# design.net
KiCad netlist of a schematic drawn in Altium Designer
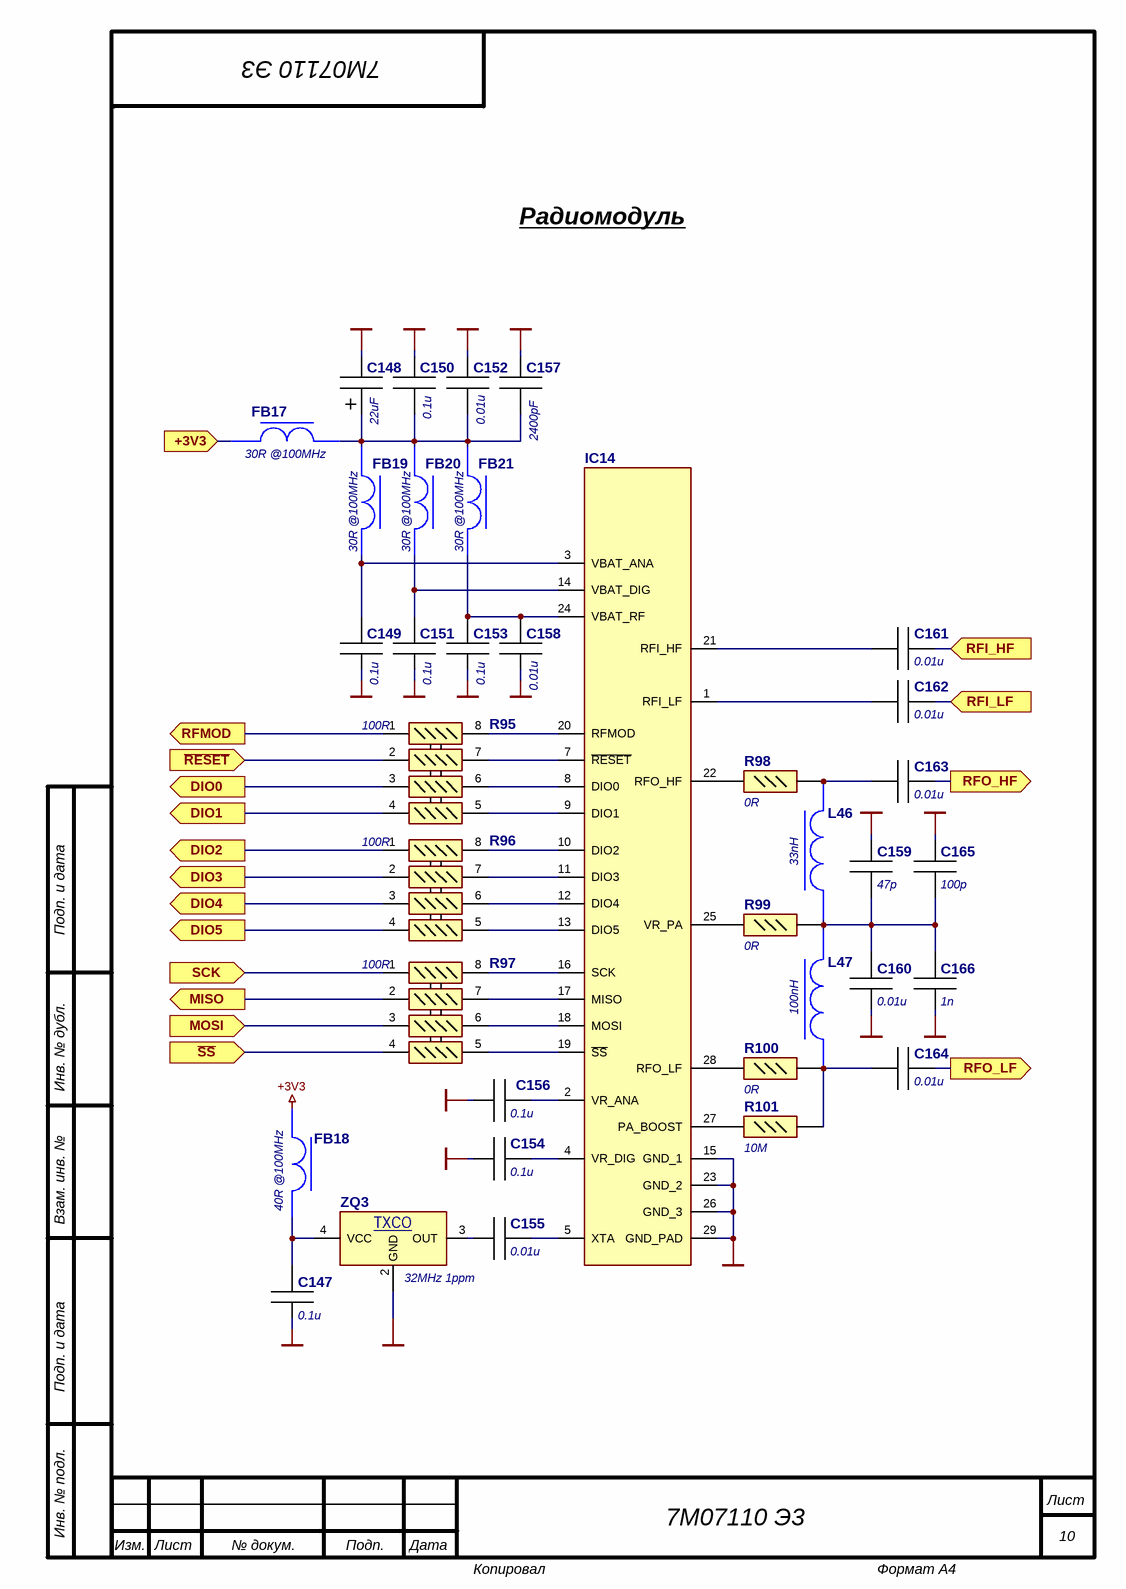
[diagram p0: Радиомодуль.SchDoc]

(export (version "E")
  (design (tool "Eeschema 10.0.6"))
  (components
    (comp (ref "C147")
      (value "0.1u")
      (footprint ":CAP0402 100x50x50")
      (description "±10% 25V Ceramic Capacitor X7R 0402 (1005 Metric)")
      (fields
        (field (name "MANUFACTURER_PART_NUMBER") "GRM155R71E104KE14J")
        (field (name "MOUSER PART NUMBER") "81-GRM155R71E104KE4J")
      )
      (libsource (lib "Capacitors 0402") (part "GRM155R71E104KE14J"))
    )
    (comp (ref "C148")
      (value "22uF")
      (footprint ":CAP1206 C3216-18")
      (description "22µF Molded Tantalum Capacitors 6.3V 1206 (3216 Metric) 300mOhm @ 100kHz")
      (fields (field (name "MANUFACTURER_PART_NUMBER") "TPSA226K006R0300"))
      (libsource (lib "Capacitors 1206") (part "TPSA226K006R0300"))
    )
    (comp (ref "C149")
      (value "0.1u")
      (footprint ":CAP0402 100x50x50")
      (description "±10% 25V Ceramic Capacitor X7R 0402 (1005 Metric)")
      (fields
        (field (name "MANUFACTURER_PART_NUMBER") "GRM155R71E104KE14J")
        (field (name "MOUSER PART NUMBER") "81-GRM155R71E104KE4J")
      )
      (libsource (lib "Capacitors 0402") (part "GRM155R71E104KE14J"))
    )
    (comp (ref "C150")
      (value "0.1u")
      (footprint ":CAP0402 100x50x50")
      (description "±10% 25V Ceramic Capacitor X7R 0402 (1005 Metric)")
      (fields
        (field (name "MANUFACTURER_PART_NUMBER") "GRM155R71E104KE14J")
        (field (name "MOUSER PART NUMBER") "81-GRM155R71E104KE4J")
      )
      (libsource (lib "Capacitors 0402") (part "GRM155R71E104KE14J"))
    )
    (comp (ref "C151")
      (value "0.1u")
      (footprint ":CAP0402 100x50x50")
      (description "±10% 25V Ceramic Capacitor X7R 0402 (1005 Metric)")
      (fields
        (field (name "MANUFACTURER_PART_NUMBER") "GRM155R71E104KE14J")
        (field (name "MOUSER PART NUMBER") "81-GRM155R71E104KE4J")
      )
      (libsource (lib "Capacitors 0402") (part "GRM155R71E104KE14J"))
    )
    (comp (ref "C152")
      (value "0.01u")
      (footprint ":CAP0402 100x50x50")
      (description "±5% 35V Ceramic Capacitor C0G, NP0 0402 (1005 Metric)")
      (fields (field (name "MANUFACTURER_PART_NUMBER") "GRM1555CYA103JE01D"))
      (libsource (lib "Capacitors 0402") (part "GRM1555CYA103JE01D"))
    )
    (comp (ref "C153")
      (value "0.1u")
      (footprint ":CAP0402 100x50x50")
      (description "±10% 25V Ceramic Capacitor X7R 0402 (1005 Metric)")
      (fields
        (field (name "MANUFACTURER_PART_NUMBER") "GRM155R71E104KE14J")
        (field (name "MOUSER PART NUMBER") "81-GRM155R71E104KE4J")
      )
      (libsource (lib "Capacitors 0402") (part "GRM155R71E104KE14J"))
    )
    (comp (ref "C154")
      (value "0.1u")
      (footprint ":CAP0402 100x50x50")
      (description "±10% 25V Ceramic Capacitor X7R 0402 (1005 Metric)")
      (fields
        (field (name "MANUFACTURER_PART_NUMBER") "GRM155R71E104KE14J")
        (field (name "MOUSER PART NUMBER") "81-GRM155R71E104KE4J")
      )
      (libsource (lib "Capacitors 0402") (part "GRM155R71E104KE14J"))
    )
    (comp (ref "C155")
      (value "0.01u")
      (footprint ":CAP0402 100x50x50")
      (description "±5% 35V Ceramic Capacitor C0G, NP0 0402 (1005 Metric)")
      (fields (field (name "MANUFACTURER_PART_NUMBER") "GRM1555CYA103JE01D"))
      (libsource (lib "Capacitors 0402") (part "GRM1555CYA103JE01D"))
    )
    (comp (ref "C156")
      (value "0.1u")
      (footprint ":CAP0402 100x50x50")
      (description "±10% 25V Ceramic Capacitor X7R 0402 (1005 Metric)")
      (fields
        (field (name "MANUFACTURER_PART_NUMBER") "GRM155R71E104KE14J")
        (field (name "MOUSER PART NUMBER") "81-GRM155R71E104KE4J")
      )
      (libsource (lib "Capacitors 0402") (part "GRM155R71E104KE14J"))
    )
    (comp (ref "C157")
      (value "2400pF")
      (footprint ":CAP0805 C2012X125")
      (description "2400pF 50V Ceramic Capacitor 0805 (2012 Metric)")
      (fields (field (name "MANUFACTURER_PART_NUMBER") "C08BL242X-5UN-X0T"))
      (libsource (lib "Capacitors 0805") (part "C08BL242X-5UN-X0T"))
    )
    (comp (ref "C158")
      (value "0.01u")
      (footprint ":CAP0402 100x50x50")
      (description "±5% 35V Ceramic Capacitor C0G, NP0 0402 (1005 Metric)")
      (fields (field (name "MANUFACTURER_PART_NUMBER") "GRM1555CYA103JE01D"))
      (libsource (lib "Capacitors 0402") (part "GRM1555CYA103JE01D"))
    )
    (comp (ref "C159")
      (value "47p")
      (footprint ":CAP0402 100x50x50")
      (description "CAP CER  50V C0G/NP0 0402")
      (fields (field (name "MANUFACTURER_PART_NUMBER") "GJM1555C1H470GB01D"))
      (libsource (lib "Capacitors 0402") (part "GJM1555C1H470GB01D"))
    )
    (comp (ref "C160")
      (value "0.01u")
      (footprint ":CAP0402 100x50x50")
      (description "±5% 35V Ceramic Capacitor C0G, NP0 0402 (1005 Metric)")
      (fields (field (name "MANUFACTURER_PART_NUMBER") "GRM1555CYA103JE01D"))
      (libsource (lib "Capacitors 0402") (part "GRM1555CYA103JE01D"))
    )
    (comp (ref "C161")
      (value "0.01u")
      (footprint ":CAP0402 100x50x50")
      (description "±5% 35V Ceramic Capacitor C0G, NP0 0402 (1005 Metric)")
      (fields (field (name "MANUFACTURER_PART_NUMBER") "GRM1555CYA103JE01D"))
      (libsource (lib "Capacitors 0402") (part "GRM1555CYA103JE01D"))
    )
    (comp (ref "C162")
      (value "0.01u")
      (footprint ":CAP0402 100x50x50")
      (description "±5% 35V Ceramic Capacitor C0G, NP0 0402 (1005 Metric)")
      (fields (field (name "MANUFACTURER_PART_NUMBER") "GRM1555CYA103JE01D"))
      (libsource (lib "Capacitors 0402") (part "GRM1555CYA103JE01D"))
    )
    (comp (ref "C163")
      (value "0.01u")
      (footprint ":CAP0402 100x50x50")
      (description "±5% 35V Ceramic Capacitor C0G, NP0 0402 (1005 Metric)")
      (fields (field (name "MANUFACTURER_PART_NUMBER") "GRM1555CYA103JE01D"))
      (libsource (lib "Capacitors 0402") (part "GRM1555CYA103JE01D"))
    )
    (comp (ref "C164")
      (value "0.01u")
      (footprint ":CAP0402 100x50x50")
      (description "±5% 35V Ceramic Capacitor C0G, NP0 0402 (1005 Metric)")
      (fields (field (name "MANUFACTURER_PART_NUMBER") "GRM1555CYA103JE01D"))
      (libsource (lib "Capacitors 0402") (part "GRM1555CYA103JE01D"))
    )
    (comp (ref "C165")
      (value "100p")
      (footprint ":CAP0402 100x50x50")
      (description "CAP CER  50V C0G/NP0 0402")
      (fields (field (name "MANUFACTURER_PART_NUMBER") "GCM1555C1H101JA16D"))
      (libsource (lib "Capacitors 0402") (part "GCM1555C1H101JA16D"))
    )
    (comp (ref "C166")
      (value "1n")
      (footprint ":CAP0402 100x50x50")
      (description "±5% 50V Ceramic Capacitor C0G, NP0 0402 (1005 Metric)")
      (fields (field (name "MANUFACTURER_PART_NUMBER") "GRM1555C1H102JA01J"))
      (libsource (lib "Capacitors 0402") (part "GRM1555C1H102JA01J"))
    )
    (comp (ref "FB17")
      (value "30R @100MHz")
      (footprint ":FER BLM18SP300SN1D")
      (description "30 Ohms @ 100MHz 1 Power Line Ferrite Bead 0603 (1608 Metric) 6A 8mOhm")
      (fields
        (field (name "MANUFACTURER_PART_NUMBER") "BLM18SP300SN1D")
        (field (name "MOUSER PART NUMBER") "81-BLM18SP300SN1D")
      )
      (libsource (lib "Ferrite Bead") (part "BLM18SP300SN1D"))
    )
    (comp (ref "FB18")
      (value "40R @100MHz")
      (footprint ":FER MMZ1005Y400CTD25")
      (description "40 Ohms @ 100MHz 1 Signal Line Ferrite Bead 0402 (1005 Metric) 550mA 100mOhm")
      (fields
        (field (name "MANUFACTURER_PART_NUMBER") "MMZ1005Y400CTD25")
        (field (name "MOUSER PART NUMBER") "810-MMZ1005Y400CTD25")
      )
      (libsource (lib "Ferrite Bead") (part "MMZ1005Y400CTD25"))
    )
    (comp (ref "FB19")
      (value "30R @100MHz")
      (footprint ":FER BLM18SP300SN1D")
      (description "30 Ohms @ 100MHz 1 Power Line Ferrite Bead 0603 (1608 Metric) 6A 8mOhm")
      (fields
        (field (name "MANUFACTURER_PART_NUMBER") "BLM18SP300SN1D")
        (field (name "MOUSER PART NUMBER") "81-BLM18SP300SN1D")
      )
      (libsource (lib "Ferrite Bead") (part "BLM18SP300SN1D"))
    )
    (comp (ref "FB20")
      (value "30R @100MHz")
      (footprint ":FER BLM18SP300SN1D")
      (description "30 Ohms @ 100MHz 1 Power Line Ferrite Bead 0603 (1608 Metric) 6A 8mOhm")
      (fields
        (field (name "MANUFACTURER_PART_NUMBER") "BLM18SP300SN1D")
        (field (name "MOUSER PART NUMBER") "81-BLM18SP300SN1D")
      )
      (libsource (lib "Ferrite Bead") (part "BLM18SP300SN1D"))
    )
    (comp (ref "FB21")
      (value "30R @100MHz")
      (footprint ":FER BLM18SP300SN1D")
      (description "30 Ohms @ 100MHz 1 Power Line Ferrite Bead 0603 (1608 Metric) 6A 8mOhm")
      (fields
        (field (name "MANUFACTURER_PART_NUMBER") "BLM18SP300SN1D")
        (field (name "MOUSER PART NUMBER") "81-BLM18SP300SN1D")
      )
      (libsource (lib "Ferrite Bead") (part "BLM18SP300SN1D"))
    )
    (comp (ref "IC14")
      (value "SX1276IMLTRT")
      (footprint ":QFN28 P600X600X100-29N-D")
      (description "LoRa RF Transceiver 3 BANDS")
      (fields (field (name "MOUSER PART NUMBER") "947-SX1276IMLTRT"))
      (libsource (lib "Digital ICs") (part "SX1276IMLTRT"))
    )
    (comp (ref "L46")
      (value "33nH")
      (footprint ":IND 0603 (1608)")
      (description "Unshielded Multilayer Inductor 0603 5%")
      (fields (field (name "MANUFACTURER_PART_NUMBER") "LQW18AN33NJ8ZD"))
      (libsource (lib "Inductance 0603") (part "LQW18AN33NJ8ZD"))
    )
    (comp (ref "L47")
      (value "100nH")
      (footprint ":IND 0603 (1608)")
      (description "Unshielded Multilayer Inductor 0603 5%")
      (fields (field (name "MANUFACTURER_PART_NUMBER") "LQW18ANR10J8ZD"))
      (libsource (lib "Inductance 0603") (part "LQW18ANR10J8ZD"))
    )
    (comp (ref "R95")
      (value "100R")
      (footprint ":RES0402x4")
      (fields
        (field (name "MANUFACTURER_PART_NUMBER") "EXB-N8V101JX")
        (field (name "MOUSER PART NUMBER") "667-EXB-N8V101JX")
      )
      (libsource (lib "Resistors Arrays") (part "EXB-N8V101JX"))
    )
    (comp (ref "R96")
      (value "100R")
      (footprint ":RES0402x4")
      (fields
        (field (name "MANUFACTURER_PART_NUMBER") "EXB-N8V101JX")
        (field (name "MOUSER PART NUMBER") "667-EXB-N8V101JX")
      )
      (libsource (lib "Resistors Arrays") (part "EXB-N8V101JX"))
    )
    (comp (ref "R97")
      (value "100R")
      (footprint ":RES0402x4")
      (fields
        (field (name "MANUFACTURER_PART_NUMBER") "EXB-N8V101JX")
        (field (name "MOUSER PART NUMBER") "667-EXB-N8V101JX")
      )
      (libsource (lib "Resistors Arrays") (part "EXB-N8V101JX"))
    )
    (comp (ref "R98")
      (value "RC0402FR-07")
      (footprint ":RES0402")
      (fields (field (name "MANUFACTURER_PART_NUMBER (PART 2: VALUE)") "0R"))
      (libsource (lib "Resistors 0402") (part "RC0402FR-07"))
    )
    (comp (ref "R99")
      (value "RC0402FR-07")
      (footprint ":RES0402")
      (fields (field (name "MANUFACTURER_PART_NUMBER (PART 2: VALUE)") "0R"))
      (libsource (lib "Resistors 0402") (part "RC0402FR-07"))
    )
    (comp (ref "R100")
      (value "RC0402FR-07")
      (footprint ":RES0402")
      (fields (field (name "MANUFACTURER_PART_NUMBER (PART 2: VALUE)") "0R"))
      (libsource (lib "Resistors 0402") (part "RC0402FR-07"))
    )
    (comp (ref "R101")
      (value "RC0402FR-07")
      (footprint ":RES0402")
      (fields (field (name "MANUFACTURER_PART_NUMBER (PART 2: VALUE)") "10M"))
      (libsource (lib "Resistors 0402") (part "RC0402FR-07"))
    )
    (comp (ref "ZQ3")
      (value "32MHz 1ppm")
      (footprint ":RESO STC22K33R48-32.000MT")
      (description "32MHz TCXO Clipped Sine Wave Oscillator 3.3V 2mA 4-SMD, \r\n-40°C ~ 85°C")
      (fields (field (name "MANUFACTURER_PART_NUMBER") "STC22K33R48-32.000MT"))
      (libsource (lib "Crystal and TXCO") (part "STC22K33R48-32.000MT"))
    )
  )
  (nets
    (net (code "1") (name "+3V3") (class "Default")
      (node (ref "FB17") (pin "1") (pinfunction "1_1") (pintype "passive"))
      (node (ref "FB18") (pin "1") (pinfunction "1_1") (pintype "passive"))
    )
    (net (code "2") (name "/DIO0") (class "Default")
      (node (ref "R95") (pin "3") (pinfunction "3_3") (pintype "passive"))
    )
    (net (code "3") (name "/DIO1") (class "Default")
      (node (ref "R95") (pin "4") (pinfunction "4_4") (pintype "passive"))
    )
    (net (code "4") (name "/DIO2") (class "Default")
      (node (ref "R96") (pin "1") (pinfunction "1_1") (pintype "passive"))
    )
    (net (code "5") (name "/DIO3") (class "Default")
      (node (ref "R96") (pin "2") (pinfunction "2_2") (pintype "passive"))
    )
    (net (code "6") (name "/DIO4") (class "Default")
      (node (ref "R96") (pin "3") (pinfunction "3_3") (pintype "passive"))
    )
    (net (code "7") (name "/DIO5") (class "Default")
      (node (ref "R96") (pin "4") (pinfunction "4_4") (pintype "passive"))
    )
    (net (code "8") (name "/MISO") (class "Default")
      (node (ref "R97") (pin "2") (pinfunction "2_2") (pintype "passive"))
    )
    (net (code "9") (name "/MOSI") (class "Default")
      (node (ref "R97") (pin "3") (pinfunction "3_3") (pintype "passive"))
    )
    (net (code "10") (name "/RFI_HF") (class "Default")
      (node (ref "C161") (pin "1") (pinfunction "1_1") (pintype "passive"))
    )
    (net (code "11") (name "/RFI_LF") (class "Default")
      (node (ref "C162") (pin "1") (pinfunction "1_1") (pintype "passive"))
    )
    (net (code "12") (name "/RFMOD") (class "Default")
      (node (ref "R95") (pin "1") (pinfunction "1_1") (pintype "passive"))
    )
    (net (code "13") (name "/RFO_HF") (class "Default")
      (node (ref "C163") (pin "1") (pinfunction "1_1") (pintype "passive"))
    )
    (net (code "14") (name "/RFO_LF") (class "Default")
      (node (ref "C164") (pin "1") (pinfunction "1_1") (pintype "passive"))
    )
    (net (code "15") (name "/SCK") (class "Default")
      (node (ref "R97") (pin "1") (pinfunction "1_1") (pintype "passive"))
    )
    (net (code "16") (name "/~{RESET}") (class "Default")
      (node (ref "R95") (pin "2") (pinfunction "2_2") (pintype "passive"))
    )
    (net (code "17") (name "/~{SS}") (class "Default")
      (node (ref "R97") (pin "4") (pinfunction "4_4") (pintype "passive"))
    )
    (net (code "18") (name "GND") (class "Default")
      (node (ref "C147") (pin "1") (pinfunction "1_1") (pintype "passive"))
      (node (ref "C148") (pin "2") (pinfunction "2_2") (pintype "passive"))
      (node (ref "C149") (pin "1") (pinfunction "1_1") (pintype "passive"))
      (node (ref "C150") (pin "2") (pinfunction "2_2") (pintype "passive"))
      (node (ref "C151") (pin "1") (pinfunction "1_1") (pintype "passive"))
      (node (ref "C152") (pin "2") (pinfunction "2_2") (pintype "passive"))
      (node (ref "C153") (pin "1") (pinfunction "1_1") (pintype "passive"))
      (node (ref "C154") (pin "1") (pinfunction "1_1") (pintype "passive"))
      (node (ref "C156") (pin "1") (pinfunction "1_1") (pintype "passive"))
      (node (ref "C157") (pin "2") (pinfunction "2_2") (pintype "passive"))
      (node (ref "C158") (pin "1") (pinfunction "1_1") (pintype "passive"))
      (node (ref "C159") (pin "1") (pinfunction "1_1") (pintype "passive"))
      (node (ref "C160") (pin "1") (pinfunction "1_1") (pintype "passive"))
      (node (ref "C165") (pin "2") (pinfunction "2_2") (pintype "passive"))
      (node (ref "C166") (pin "1") (pinfunction "1_1") (pintype "passive"))
      (node (ref "IC14") (pin "15") (pinfunction "GND_1_15") (pintype "passive"))
      (node (ref "IC14") (pin "23") (pinfunction "GND_2_23") (pintype "passive"))
      (node (ref "IC14") (pin "26") (pinfunction "GND_3_26") (pintype "passive"))
      (node (ref "IC14") (pin "29") (pinfunction "GND_PAD_29") (pintype "passive"))
      (node (ref "ZQ3") (pin "2") (pinfunction "GND_2") (pintype "passive"))
    )
    (net (code "19") (name "Net-(C148-+)") (class "Default")
      (node (ref "C148") (pin "1") (pinfunction "+_1") (pintype "passive"))
      (node (ref "C150") (pin "1") (pinfunction "1_1") (pintype "passive"))
      (node (ref "C152") (pin "1") (pinfunction "1_1") (pintype "passive"))
      (node (ref "C157") (pin "1") (pinfunction "1_1") (pintype "passive"))
      (node (ref "FB17") (pin "2") (pinfunction "2_2") (pintype "passive"))
      (node (ref "FB19") (pin "1") (pinfunction "1_1") (pintype "passive"))
      (node (ref "FB20") (pin "1") (pinfunction "1_1") (pintype "passive"))
      (node (ref "FB21") (pin "1") (pinfunction "1_1") (pintype "passive"))
    )
    (net (code "20") (name "Net-(C159-Pad2)") (class "Default")
      (node (ref "C159") (pin "2") (pinfunction "2_2") (pintype "passive"))
      (node (ref "C160") (pin "2") (pinfunction "2_2") (pintype "passive"))
      (node (ref "C165") (pin "1") (pinfunction "1_1") (pintype "passive"))
      (node (ref "C166") (pin "2") (pinfunction "2_2") (pintype "passive"))
      (node (ref "L46") (pin "1") (pinfunction "1_1") (pintype "passive"))
      (node (ref "L47") (pin "1") (pinfunction "1_1") (pintype "passive"))
      (node (ref "R99") (pin "1") (pinfunction "1_1") (pintype "passive"))
    )
    (net (code "21") (name "Net-(C163-Pad2)") (class "Default")
      (node (ref "C163") (pin "2") (pinfunction "2_2") (pintype "passive"))
      (node (ref "L46") (pin "2") (pinfunction "2_2") (pintype "passive"))
      (node (ref "R98") (pin "1") (pinfunction "1_1") (pintype "passive"))
    )
    (net (code "22") (name "Net-(C164-Pad2)") (class "Default")
      (node (ref "C164") (pin "2") (pinfunction "2_2") (pintype "passive"))
      (node (ref "L47") (pin "2") (pinfunction "2_2") (pintype "passive"))
      (node (ref "R100") (pin "1") (pinfunction "1_1") (pintype "passive"))
      (node (ref "R101") (pin "1") (pinfunction "1_1") (pintype "passive"))
    )
    (net (code "23") (name "Net-(IC14-DIO0)") (class "Default")
      (node (ref "IC14") (pin "8") (pinfunction "DIO0_8") (pintype "passive"))
      (node (ref "R95") (pin "6") (pinfunction "6_6") (pintype "passive"))
    )
    (net (code "24") (name "Net-(IC14-DIO1)") (class "Default")
      (node (ref "IC14") (pin "9") (pinfunction "DIO1_9") (pintype "passive"))
      (node (ref "R95") (pin "5") (pinfunction "5_5") (pintype "passive"))
    )
    (net (code "25") (name "Net-(IC14-DIO2)") (class "Default")
      (node (ref "IC14") (pin "10") (pinfunction "DIO2_10") (pintype "passive"))
      (node (ref "R96") (pin "8") (pinfunction "8_8") (pintype "passive"))
    )
    (net (code "26") (name "Net-(IC14-DIO3)") (class "Default")
      (node (ref "IC14") (pin "11") (pinfunction "DIO3_11") (pintype "passive"))
      (node (ref "R96") (pin "7") (pinfunction "7_7") (pintype "passive"))
    )
    (net (code "27") (name "Net-(IC14-DIO4)") (class "Default")
      (node (ref "IC14") (pin "12") (pinfunction "DIO4_12") (pintype "passive"))
      (node (ref "R96") (pin "6") (pinfunction "6_6") (pintype "passive"))
    )
    (net (code "28") (name "Net-(IC14-DIO5)") (class "Default")
      (node (ref "IC14") (pin "13") (pinfunction "DIO5_13") (pintype "passive"))
      (node (ref "R96") (pin "5") (pinfunction "5_5") (pintype "passive"))
    )
    (net (code "29") (name "Net-(IC14-MISO)") (class "Default")
      (node (ref "IC14") (pin "17") (pinfunction "MISO_17") (pintype "passive"))
      (node (ref "R97") (pin "7") (pinfunction "7_7") (pintype "passive"))
    )
    (net (code "30") (name "Net-(IC14-MOSI)") (class "Default")
      (node (ref "IC14") (pin "18") (pinfunction "MOSI_18") (pintype "passive"))
      (node (ref "R97") (pin "6") (pinfunction "6_6") (pintype "passive"))
    )
    (net (code "31") (name "Net-(IC14-PA_BOOST)") (class "Default")
      (node (ref "IC14") (pin "27") (pinfunction "PA_BOOST_27") (pintype "passive"))
      (node (ref "R101") (pin "2") (pinfunction "2_2") (pintype "passive"))
    )
    (net (code "32") (name "Net-(IC14-RFI_HF)") (class "Default")
      (node (ref "C161") (pin "2") (pinfunction "2_2") (pintype "passive"))
      (node (ref "IC14") (pin "21") (pinfunction "RFI_HF_21") (pintype "passive"))
    )
    (net (code "33") (name "Net-(IC14-RFI_LF)") (class "Default")
      (node (ref "C162") (pin "2") (pinfunction "2_2") (pintype "passive"))
      (node (ref "IC14") (pin "1") (pinfunction "RFI_LF_1") (pintype "passive"))
    )
    (net (code "34") (name "Net-(IC14-RFMOD)") (class "Default")
      (node (ref "IC14") (pin "20") (pinfunction "RFMOD_20") (pintype "passive"))
      (node (ref "R95") (pin "8") (pinfunction "8_8") (pintype "passive"))
    )
    (net (code "35") (name "Net-(IC14-RFO_HF)") (class "Default")
      (node (ref "IC14") (pin "22") (pinfunction "RFO_HF_22") (pintype "passive"))
      (node (ref "R98") (pin "2") (pinfunction "2_2") (pintype "passive"))
    )
    (net (code "36") (name "Net-(IC14-RFO_LF)") (class "Default")
      (node (ref "IC14") (pin "28") (pinfunction "RFO_LF_28") (pintype "passive"))
      (node (ref "R100") (pin "2") (pinfunction "2_2") (pintype "passive"))
    )
    (net (code "37") (name "Net-(IC14-SCK)") (class "Default")
      (node (ref "IC14") (pin "16") (pinfunction "SCK_16") (pintype "passive"))
      (node (ref "R97") (pin "8") (pinfunction "8_8") (pintype "passive"))
    )
    (net (code "38") (name "Net-(IC14-VBAT_ANA)") (class "Default")
      (node (ref "C149") (pin "2") (pinfunction "2_2") (pintype "passive"))
      (node (ref "FB19") (pin "2") (pinfunction "2_2") (pintype "passive"))
      (node (ref "IC14") (pin "3") (pinfunction "VBAT_ANA_3") (pintype "passive"))
    )
    (net (code "39") (name "Net-(IC14-VBAT_DIG)") (class "Default")
      (node (ref "C151") (pin "2") (pinfunction "2_2") (pintype "passive"))
      (node (ref "FB20") (pin "2") (pinfunction "2_2") (pintype "passive"))
      (node (ref "IC14") (pin "14") (pinfunction "VBAT_DIG_14") (pintype "passive"))
    )
    (net (code "40") (name "Net-(IC14-VBAT_RF)") (class "Default")
      (node (ref "C153") (pin "2") (pinfunction "2_2") (pintype "passive"))
      (node (ref "C158") (pin "2") (pinfunction "2_2") (pintype "passive"))
      (node (ref "FB21") (pin "2") (pinfunction "2_2") (pintype "passive"))
      (node (ref "IC14") (pin "24") (pinfunction "VBAT_RF_24") (pintype "passive"))
    )
    (net (code "41") (name "Net-(IC14-VR_ANA)") (class "Default")
      (node (ref "C156") (pin "2") (pinfunction "2_2") (pintype "passive"))
      (node (ref "IC14") (pin "2") (pinfunction "VR_ANA_2") (pintype "passive"))
    )
    (net (code "42") (name "Net-(IC14-VR_DIG)") (class "Default")
      (node (ref "C154") (pin "2") (pinfunction "2_2") (pintype "passive"))
      (node (ref "IC14") (pin "4") (pinfunction "VR_DIG_4") (pintype "passive"))
    )
    (net (code "43") (name "Net-(IC14-VR_PA)") (class "Default")
      (node (ref "IC14") (pin "25") (pinfunction "VR_PA_25") (pintype "passive"))
      (node (ref "R99") (pin "2") (pinfunction "2_2") (pintype "passive"))
    )
    (net (code "44") (name "Net-(IC14-XTA)") (class "Default")
      (node (ref "C155") (pin "1") (pinfunction "1_1") (pintype "passive"))
      (node (ref "IC14") (pin "5") (pinfunction "XTA_5") (pintype "passive"))
    )
    (net (code "45") (name "Net-(IC14-~{RESET})") (class "Default")
      (node (ref "IC14") (pin "7") (pinfunction "~{RESET}_7") (pintype "passive"))
      (node (ref "R95") (pin "7") (pinfunction "7_7") (pintype "passive"))
    )
    (net (code "46") (name "Net-(IC14-~{SS})") (class "Default")
      (node (ref "IC14") (pin "19") (pinfunction "~{SS}_19") (pintype "passive"))
      (node (ref "R97") (pin "5") (pinfunction "5_5") (pintype "passive"))
    )
    (net (code "47") (name "Net-(ZQ3-OUT)") (class "Default")
      (node (ref "C155") (pin "2") (pinfunction "2_2") (pintype "passive"))
      (node (ref "ZQ3") (pin "3") (pinfunction "OUT_3") (pintype "passive"))
    )
    (net (code "48") (name "Net-(ZQ3-VCC)") (class "Default")
      (node (ref "C147") (pin "2") (pinfunction "2_2") (pintype "passive"))
      (node (ref "FB18") (pin "2") (pinfunction "2_2") (pintype "passive"))
      (node (ref "ZQ3") (pin "4") (pinfunction "VCC_4") (pintype "passive"))
    )
  )
)
